# Peripherals.net
KiCad netlist of a schematic drawn in Altium Designer
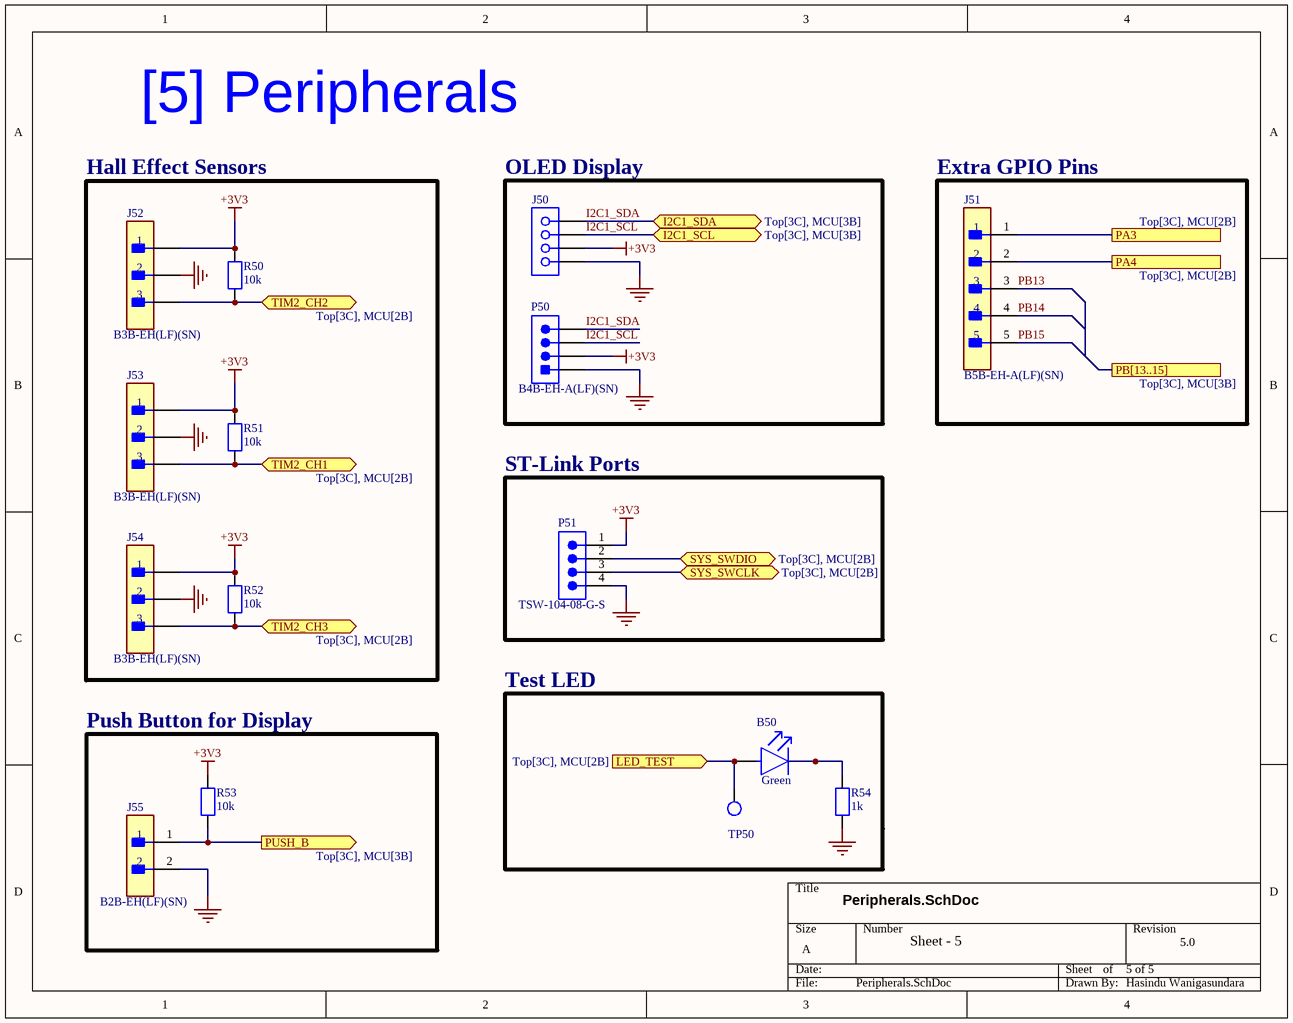
[diagram p0: Peripherals.SchDoc]

(export (version "E")
  (design (tool "Eeschema 10.0.6"))
  (components
    (comp (ref "B50")
      (value "Green")
      (footprint "FP-LTST-C171GKT-MFG")
      (description "LED GREEN CLEAR CHIP SMD")
      (libsource (lib "Altium Content Vault") (part "8706943c75ba83719d021d2fdc84c58"))
    )
    (comp (ref "J50")
      (value "61300411821")
      (footprint "61300411821")
      (description "THT Vertical Socket Header WR-PHD, Pitch 2.54 mm, Single Row, 4 pins")
      (libsource (lib "Altium Content Vault") (part "Header_Female_1R_04P"))
    )
    (comp (ref "J51")
      (value "B5B-EH-A(LF)(SN)")
      (footprint "FP-B5B-EH-A_LF_SN-MFG")
      (description "CONN HEADER VERT 5POS 2.5MM")
      (libsource (lib "Altium Content Vault") (part "bf93c07fd2649a848d0ec8585582aab"))
    )
    (comp (ref "J52")
      (value "B3B-EH(LF)(SN)")
      (footprint "FP-B3B-EH_LF_SN-MFG")
      (description "3 Position Single Row 2.5 mm Press Fit Through Hole Shrouded Pin Header")
      (libsource (lib "Altium Content Vault") (part "0d3f023dd272f625e17a2be33dea85f"))
    )
    (comp (ref "J53")
      (value "B3B-EH(LF)(SN)")
      (footprint "FP-B3B-EH_LF_SN-MFG")
      (description "3 Position Single Row 2.5 mm Press Fit Through Hole Shrouded Pin Header")
      (libsource (lib "Altium Content Vault") (part "0d3f023dd272f625e17a2be33dea85f"))
    )
    (comp (ref "J54")
      (value "B3B-EH(LF)(SN)")
      (footprint "FP-B3B-EH_LF_SN-MFG")
      (description "3 Position Single Row 2.5 mm Press Fit Through Hole Shrouded Pin Header")
      (libsource (lib "Altium Content Vault") (part "0d3f023dd272f625e17a2be33dea85f"))
    )
    (comp (ref "J55")
      (value "B2B-EH(LF)(SN)")
      (footprint "FP-B2B-EH_LF_SN-MFG")
      (description "Connector Header, EH Series, 2 Position, 2.5mm, Through Hole, Press-Fit, Solder, Natural")
      (libsource (lib "Altium Content Vault") (part "3bc925449376181038e59eaffc5286c"))
    )
    (comp (ref "P50")
      (value "B4B-EH-A(LF)(SN)")
      (footprint "JST-B4B-EH-A_V")
      (fields (field (name "MANUFACTURER") "JST"))
      (libsource (lib "Altium Content Vault") (part "CN-1P-M-R4"))
    )
    (comp (ref "P51")
      (value "TSW-104-08-G-S")
      (footprint "SMTC-TSW-104-08-X-S")
      (description "0.025\" SQ Post Header, Through-hole, Vertical, -55 to 125 degC, 2.54 mm Pitch, 4-Pin, Male, RoHS")
      (fields (field (name "MANUFACTURER") "Samtec"))
      (libsource (lib "Altium Content Vault") (part "SMTC-TSW-104-08-X-S"))
    )
    (comp (ref "R50")
      (value "10k")
      (footprint "RES_1206")
      (description "SMD 3.2mm × 1.6mm size resistor (1206)")
      (libsource (lib "EDR - Water Meter") (part "RES_1206"))
    )
    (comp (ref "R51")
      (value "10k")
      (footprint "RES_1206")
      (description "SMD 3.2mm × 1.6mm size resistor (1206)")
      (libsource (lib "EDR - Water Meter") (part "RES_1206"))
    )
    (comp (ref "R52")
      (value "10k")
      (footprint "RES_1206")
      (description "SMD 3.2mm × 1.6mm size resistor (1206)")
      (libsource (lib "EDR - Water Meter") (part "RES_1206"))
    )
    (comp (ref "R53")
      (value "10k")
      (footprint "RES_1206")
      (description "SMD 3.2mm × 1.6mm size resistor (1206)")
      (libsource (lib "EDR - Water Meter") (part "RES_1206"))
    )
    (comp (ref "R54")
      (value "1k")
      (footprint "RES_1206")
      (description "SMD 3.2mm × 1.6mm size resistor (1206)")
      (libsource (lib "EDR - Water Meter") (part "RES_1206"))
    )
    (comp (ref "TP50")
      (value "Test Pad")
      (footprint "Test Pad")
      (libsource (lib "EDR - Water Meter") (part "Test Pad"))
    )
  )
  (nets
    (net (code "1") (name "+3V3") (class "Default")
      (node (ref "J50") (pin "2") (pinfunction "2_2") (pintype "passive"))
      (node (ref "J52") (pin "1") (pinfunction "1_1") (pintype "passive"))
      (node (ref "J53") (pin "1") (pinfunction "1_1") (pintype "passive"))
      (node (ref "J54") (pin "1") (pinfunction "1_1") (pintype "passive"))
      (node (ref "P50") (pin "2") (pinfunction "2_2") (pintype "passive"))
      (node (ref "P51") (pin "1") (pinfunction "1_1") (pintype "passive"))
      (node (ref "R50") (pin "2") (pintype "passive"))
      (node (ref "R51") (pin "2") (pintype "passive"))
      (node (ref "R52") (pin "2") (pintype "passive"))
      (node (ref "R53") (pin "2") (pintype "passive"))
    )
    (net (code "2") (name "/I2C1_SCL") (class "Default")
      (node (ref "J50") (pin "3") (pinfunction "3_3") (pintype "passive"))
      (node (ref "P50") (pin "3") (pinfunction "3_3") (pintype "passive"))
    )
    (net (code "3") (name "/I2C1_SDA") (class "Default")
      (node (ref "J50") (pin "4") (pinfunction "4_4") (pintype "passive"))
      (node (ref "P50") (pin "4") (pinfunction "4_4") (pintype "passive"))
    )
    (net (code "4") (name "/LED_TEST") (class "Default")
      (node (ref "B50") (pin "2") (pinfunction "A_2") (pintype "passive"))
      (node (ref "TP50") (pin "1") (pintype "passive"))
    )
    (net (code "5") (name "/PA3") (class "Default")
      (node (ref "J51") (pin "1") (pinfunction "1_1") (pintype "passive"))
    )
    (net (code "6") (name "/PA4") (class "Default")
      (node (ref "J51") (pin "2") (pinfunction "2_2") (pintype "passive"))
    )
    (net (code "7") (name "/PB13") (class "Default")
      (node (ref "J51") (pin "3") (pinfunction "3_3") (pintype "passive"))
    )
    (net (code "8") (name "/PB14") (class "Default")
      (node (ref "J51") (pin "4") (pinfunction "4_4") (pintype "passive"))
    )
    (net (code "9") (name "/PB15") (class "Default")
      (node (ref "J51") (pin "5") (pinfunction "5_5") (pintype "passive"))
    )
    (net (code "11") (name "/PUSH_B") (class "Default")
      (node (ref "J55") (pin "1") (pinfunction "1_1") (pintype "passive"))
      (node (ref "R53") (pin "1") (pintype "passive"))
    )
    (net (code "12") (name "/SYS_SWCLK") (class "Default")
      (node (ref "P51") (pin "3") (pinfunction "3_3") (pintype "passive"))
    )
    (net (code "13") (name "/SYS_SWDIO") (class "Default")
      (node (ref "P51") (pin "2") (pinfunction "2_2") (pintype "passive"))
    )
    (net (code "14") (name "/TIM2_CH1") (class "Default")
      (node (ref "J53") (pin "3") (pinfunction "3_3") (pintype "passive"))
      (node (ref "R51") (pin "1") (pintype "passive"))
    )
    (net (code "15") (name "/TIM2_CH2") (class "Default")
      (node (ref "J52") (pin "3") (pinfunction "3_3") (pintype "passive"))
      (node (ref "R50") (pin "1") (pintype "passive"))
    )
    (net (code "16") (name "/TIM2_CH3") (class "Default")
      (node (ref "J54") (pin "3") (pinfunction "3_3") (pintype "passive"))
      (node (ref "R52") (pin "1") (pintype "passive"))
    )
    (net (code "17") (name "GND") (class "Default")
      (node (ref "J50") (pin "1") (pinfunction "1_1") (pintype "passive"))
      (node (ref "J52") (pin "2") (pinfunction "2_2") (pintype "passive"))
      (node (ref "J53") (pin "2") (pinfunction "2_2") (pintype "passive"))
      (node (ref "J54") (pin "2") (pinfunction "2_2") (pintype "passive"))
      (node (ref "J55") (pin "2") (pinfunction "2_2") (pintype "passive"))
      (node (ref "P50") (pin "1") (pinfunction "1_1") (pintype "passive"))
      (node (ref "P51") (pin "4") (pinfunction "4_4") (pintype "passive"))
      (node (ref "R54") (pin "1") (pintype "passive"))
    )
    (net (code "18") (name "Net-(B50-C)") (class "Default")
      (node (ref "B50") (pin "1") (pinfunction "C_1") (pintype "passive"))
      (node (ref "R54") (pin "2") (pintype "passive"))
    )
  )
)
